# SSv3_outputAmp.net
KiCad netlist of a schematic drawn in EAGLE
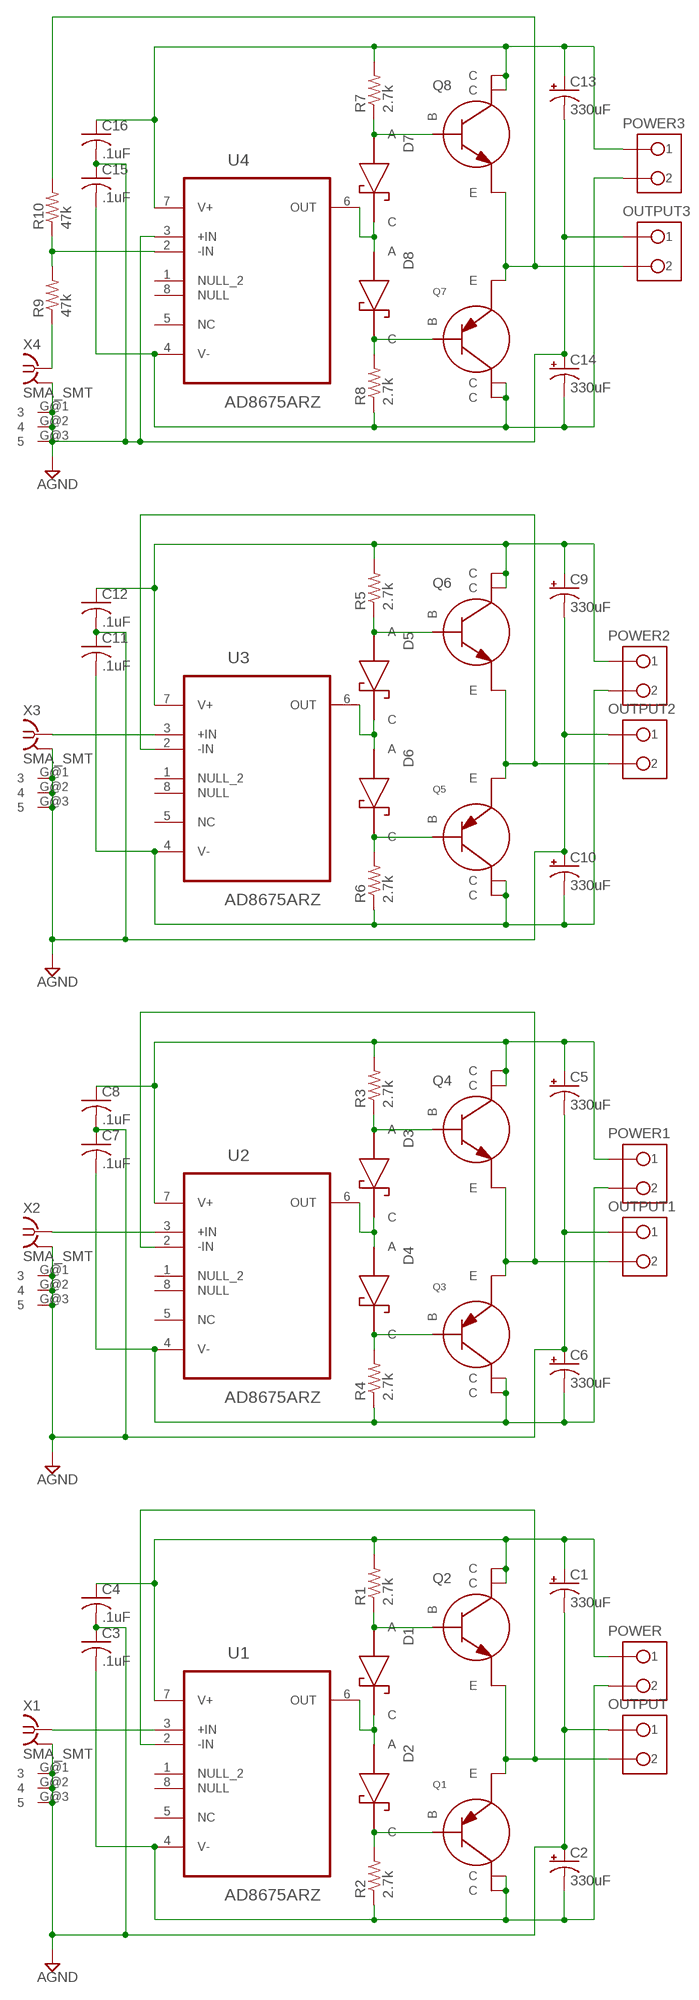
[diagram p0: schematic, sheet 1]

(export (version "E")
  (design (tool "Eeschema 10.0.6"))
  (components
    (comp (ref "C1")
      (value "330uF")
      (footprint "eagle-import:E3,5-8")
      (libsource (lib "eagle-import") (part "CPOL-USE3.5-8"))
    )
    (comp (ref "C2")
      (value "330uF")
      (footprint "eagle-import:E3,5-8")
      (libsource (lib "eagle-import") (part "CPOL-USE3.5-8"))
    )
    (comp (ref "C3")
      (value ".1uF")
      (footprint "eagle-import:C0603")
      (libsource (lib "eagle-import") (part "C-USC0603"))
    )
    (comp (ref "C4")
      (value ".1uF")
      (footprint "eagle-import:C0603")
      (libsource (lib "eagle-import") (part "C-USC0603"))
    )
    (comp (ref "C5")
      (value "330uF")
      (footprint "eagle-import:E3,5-8")
      (libsource (lib "eagle-import") (part "CPOL-USE3.5-8"))
    )
    (comp (ref "C6")
      (value "330uF")
      (footprint "eagle-import:E3,5-8")
      (libsource (lib "eagle-import") (part "CPOL-USE3.5-8"))
    )
    (comp (ref "C7")
      (value ".1uF")
      (footprint "eagle-import:C0603")
      (libsource (lib "eagle-import") (part "C-USC0603"))
    )
    (comp (ref "C8")
      (value ".1uF")
      (footprint "eagle-import:C0603")
      (libsource (lib "eagle-import") (part "C-USC0603"))
    )
    (comp (ref "C9")
      (value "330uF")
      (footprint "eagle-import:E3,5-8")
      (libsource (lib "eagle-import") (part "CPOL-USE3.5-8"))
    )
    (comp (ref "C10")
      (value "330uF")
      (footprint "eagle-import:E3,5-8")
      (libsource (lib "eagle-import") (part "CPOL-USE3.5-8"))
    )
    (comp (ref "C11")
      (value ".1uF")
      (footprint "eagle-import:C0603")
      (libsource (lib "eagle-import") (part "C-USC0603"))
    )
    (comp (ref "C12")
      (value ".1uF")
      (footprint "eagle-import:C0603")
      (libsource (lib "eagle-import") (part "C-USC0603"))
    )
    (comp (ref "C13")
      (value "330uF")
      (footprint "eagle-import:E3,5-8")
      (libsource (lib "eagle-import") (part "CPOL-USE3.5-8"))
    )
    (comp (ref "C14")
      (value "330uF")
      (footprint "eagle-import:E3,5-8")
      (libsource (lib "eagle-import") (part "CPOL-USE3.5-8"))
    )
    (comp (ref "C15")
      (value ".1uF")
      (footprint "eagle-import:C0603")
      (libsource (lib "eagle-import") (part "C-USC0603"))
    )
    (comp (ref "C16")
      (value ".1uF")
      (footprint "eagle-import:C0603")
      (libsource (lib "eagle-import") (part "C-USC0603"))
    )
    (comp (ref "D1")
      (value "1N5819SOD123")
      (footprint "eagle-import:SOD-123")
      (libsource (lib "eagle-import") (part "1N5819SOD123"))
    )
    (comp (ref "D2")
      (value "1N5819SOD123")
      (footprint "eagle-import:SOD-123")
      (libsource (lib "eagle-import") (part "1N5819SOD123"))
    )
    (comp (ref "D3")
      (value "1N5819SOD123")
      (footprint "eagle-import:SOD-123")
      (libsource (lib "eagle-import") (part "1N5819SOD123"))
    )
    (comp (ref "D4")
      (value "1N5819SOD123")
      (footprint "eagle-import:SOD-123")
      (libsource (lib "eagle-import") (part "1N5819SOD123"))
    )
    (comp (ref "D5")
      (value "1N5819SOD123")
      (footprint "eagle-import:SOD-123")
      (libsource (lib "eagle-import") (part "1N5819SOD123"))
    )
    (comp (ref "D6")
      (value "1N5819SOD123")
      (footprint "eagle-import:SOD-123")
      (libsource (lib "eagle-import") (part "1N5819SOD123"))
    )
    (comp (ref "D7")
      (value "1N5819SOD123")
      (footprint "eagle-import:SOD-123")
      (libsource (lib "eagle-import") (part "1N5819SOD123"))
    )
    (comp (ref "D8")
      (value "1N5819SOD123")
      (footprint "eagle-import:SOD-123")
      (libsource (lib "eagle-import") (part "1N5819SOD123"))
    )
    (comp (ref "OUTPUT")
      (value "OST-2P-SCREW-TERMINAL")
      (footprint "eagle-import:OST-2P-SCREW-TERMINAL")
      (libsource (lib "eagle-import") (part "OST-2P-SCREW-TERMINAL"))
    )
    (comp (ref "OUTPUT1")
      (value "OST-2P-SCREW-TERMINAL")
      (footprint "eagle-import:OST-2P-SCREW-TERMINAL")
      (libsource (lib "eagle-import") (part "OST-2P-SCREW-TERMINAL"))
    )
    (comp (ref "OUTPUT2")
      (value "OST-2P-SCREW-TERMINAL")
      (footprint "eagle-import:OST-2P-SCREW-TERMINAL")
      (libsource (lib "eagle-import") (part "OST-2P-SCREW-TERMINAL"))
    )
    (comp (ref "OUTPUT3")
      (value "OST-2P-SCREW-TERMINAL")
      (footprint "eagle-import:OST-2P-SCREW-TERMINAL")
      (libsource (lib "eagle-import") (part "OST-2P-SCREW-TERMINAL"))
    )
    (comp (ref "POWER")
      (value "OST-2P-SCREW-TERMINAL")
      (footprint "eagle-import:OST-2P-SCREW-TERMINAL")
      (libsource (lib "eagle-import") (part "OST-2P-SCREW-TERMINAL"))
    )
    (comp (ref "POWER1")
      (value "OST-2P-SCREW-TERMINAL")
      (footprint "eagle-import:OST-2P-SCREW-TERMINAL")
      (libsource (lib "eagle-import") (part "OST-2P-SCREW-TERMINAL"))
    )
    (comp (ref "POWER2")
      (value "OST-2P-SCREW-TERMINAL")
      (footprint "eagle-import:OST-2P-SCREW-TERMINAL")
      (libsource (lib "eagle-import") (part "OST-2P-SCREW-TERMINAL"))
    )
    (comp (ref "POWER3")
      (value "OST-2P-SCREW-TERMINAL")
      (footprint "eagle-import:OST-2P-SCREW-TERMINAL")
      (libsource (lib "eagle-import") (part "OST-2P-SCREW-TERMINAL"))
    )
    (comp (ref "Q1")
      (value "NJT4030PSOT-223")
      (footprint "eagle-import:SOT223")
      (libsource (lib "eagle-import") (part "NJT4030PSOT-223"))
    )
    (comp (ref "Q2")
      (value "NJT4031NSOT-223")
      (footprint "eagle-import:SOT223")
      (libsource (lib "eagle-import") (part "NJT4031NSOT-223"))
    )
    (comp (ref "Q3")
      (value "NJT4030PSOT-223")
      (footprint "eagle-import:SOT223")
      (libsource (lib "eagle-import") (part "NJT4030PSOT-223"))
    )
    (comp (ref "Q4")
      (value "NJT4031NSOT-223")
      (footprint "eagle-import:SOT223")
      (libsource (lib "eagle-import") (part "NJT4031NSOT-223"))
    )
    (comp (ref "Q5")
      (value "NJT4030PSOT-223")
      (footprint "eagle-import:SOT223")
      (libsource (lib "eagle-import") (part "NJT4030PSOT-223"))
    )
    (comp (ref "Q6")
      (value "NJT4031NSOT-223")
      (footprint "eagle-import:SOT223")
      (libsource (lib "eagle-import") (part "NJT4031NSOT-223"))
    )
    (comp (ref "Q7")
      (value "NJT4030PSOT-223")
      (footprint "eagle-import:SOT223")
      (libsource (lib "eagle-import") (part "NJT4030PSOT-223"))
    )
    (comp (ref "Q8")
      (value "NJT4031NSOT-223")
      (footprint "eagle-import:SOT223")
      (libsource (lib "eagle-import") (part "NJT4031NSOT-223"))
    )
    (comp (ref "R1")
      (value "2.7k")
      (footprint "eagle-import:R0603")
      (libsource (lib "eagle-import") (part "R-US_R0603"))
    )
    (comp (ref "R2")
      (value "2.7k")
      (footprint "eagle-import:R0603")
      (libsource (lib "eagle-import") (part "R-US_R0603"))
    )
    (comp (ref "R3")
      (value "2.7k")
      (footprint "eagle-import:R0603")
      (libsource (lib "eagle-import") (part "R-US_R0603"))
    )
    (comp (ref "R4")
      (value "2.7k")
      (footprint "eagle-import:R0603")
      (libsource (lib "eagle-import") (part "R-US_R0603"))
    )
    (comp (ref "R5")
      (value "2.7k")
      (footprint "eagle-import:R0603")
      (libsource (lib "eagle-import") (part "R-US_R0603"))
    )
    (comp (ref "R6")
      (value "2.7k")
      (footprint "eagle-import:R0603")
      (libsource (lib "eagle-import") (part "R-US_R0603"))
    )
    (comp (ref "R7")
      (value "2.7k")
      (footprint "eagle-import:R0603")
      (libsource (lib "eagle-import") (part "R-US_R0603"))
    )
    (comp (ref "R8")
      (value "2.7k")
      (footprint "eagle-import:R0603")
      (libsource (lib "eagle-import") (part "R-US_R0603"))
    )
    (comp (ref "R9")
      (value "47k")
      (footprint "eagle-import:R0603")
      (libsource (lib "eagle-import") (part "R-US_R0603"))
    )
    (comp (ref "R10")
      (value "47k")
      (footprint "eagle-import:R0603")
      (libsource (lib "eagle-import") (part "R-US_R0603"))
    )
    (comp (ref "U1")
      (value "AD8675ARZ")
      (footprint "eagle-import:SOIC127P600X175-8N")
      (libsource (lib "eagle-import") (part "AD8675ARZ"))
    )
    (comp (ref "U2")
      (value "AD8675ARZ")
      (footprint "eagle-import:SOIC127P600X175-8N")
      (libsource (lib "eagle-import") (part "AD8675ARZ"))
    )
    (comp (ref "U3")
      (value "AD8675ARZ")
      (footprint "eagle-import:SOIC127P600X175-8N")
      (libsource (lib "eagle-import") (part "AD8675ARZ"))
    )
    (comp (ref "U4")
      (value "AD8675ARZ")
      (footprint "eagle-import:SOIC127P600X175-8N")
      (libsource (lib "eagle-import") (part "AD8675ARZ"))
    )
    (comp (ref "X1")
      (value "SMA_SMT")
      (footprint "eagle-import:SIDE_MOUNTSMA")
      (libsource (lib "eagle-import") (part "SMA_SMT"))
    )
    (comp (ref "X2")
      (value "SMA_SMT")
      (footprint "eagle-import:SIDE_MOUNTSMA")
      (libsource (lib "eagle-import") (part "SMA_SMT"))
    )
    (comp (ref "X3")
      (value "SMA_SMT")
      (footprint "eagle-import:SIDE_MOUNTSMA")
      (libsource (lib "eagle-import") (part "SMA_SMT"))
    )
    (comp (ref "X4")
      (value "SMA_SMT")
      (footprint "eagle-import:SIDE_MOUNTSMA")
      (libsource (lib "eagle-import") (part "SMA_SMT"))
    )
  )
  (nets
    (net (code "1") (name "/+12V") (class "Default")
      (node (ref "C1") (pin "+") (pinfunction "+_+") (pintype "passive"))
      (node (ref "C12") (pin "1") (pinfunction "1_1") (pintype "passive"))
      (node (ref "C13") (pin "+") (pinfunction "+_+") (pintype "passive"))
      (node (ref "C16") (pin "1") (pinfunction "1_1") (pintype "passive"))
      (node (ref "C4") (pin "1") (pinfunction "1_1") (pintype "passive"))
      (node (ref "C5") (pin "+") (pinfunction "+_+") (pintype "passive"))
      (node (ref "C8") (pin "1") (pinfunction "1_1") (pintype "passive"))
      (node (ref "C9") (pin "+") (pinfunction "+_+") (pintype "passive"))
      (node (ref "POWER") (pin "P$1") (pinfunction "1_P$1") (pintype "bidirectional"))
      (node (ref "POWER1") (pin "P$1") (pinfunction "1_P$1") (pintype "bidirectional"))
      (node (ref "POWER2") (pin "P$1") (pinfunction "1_P$1") (pintype "bidirectional"))
      (node (ref "POWER3") (pin "P$1") (pinfunction "1_P$1") (pintype "bidirectional"))
      (node (ref "Q2") (pin "2") (pinfunction "C_2") (pintype "bidirectional"))
      (node (ref "Q2") (pin "4") (pinfunction "C_4") (pintype "bidirectional"))
      (node (ref "Q4") (pin "2") (pinfunction "C_2") (pintype "bidirectional"))
      (node (ref "Q4") (pin "4") (pinfunction "C_4") (pintype "bidirectional"))
      (node (ref "Q6") (pin "2") (pinfunction "C_2") (pintype "bidirectional"))
      (node (ref "Q6") (pin "4") (pinfunction "C_4") (pintype "bidirectional"))
      (node (ref "Q8") (pin "2") (pinfunction "C_2") (pintype "bidirectional"))
      (node (ref "Q8") (pin "4") (pinfunction "C_4") (pintype "bidirectional"))
      (node (ref "R1") (pin "2") (pinfunction "2_2") (pintype "passive"))
      (node (ref "R3") (pin "2") (pinfunction "2_2") (pintype "passive"))
      (node (ref "R5") (pin "2") (pinfunction "2_2") (pintype "passive"))
      (node (ref "R7") (pin "2") (pinfunction "2_2") (pintype "passive"))
      (node (ref "U1") (pin "7") (pinfunction "V+_7") (pintype "power_in"))
      (node (ref "U2") (pin "7") (pinfunction "V+_7") (pintype "power_in"))
      (node (ref "U3") (pin "7") (pinfunction "V+_7") (pintype "power_in"))
      (node (ref "U4") (pin "7") (pinfunction "V+_7") (pintype "power_in"))
    )
    (net (code "2") (name "/-12V") (class "Default")
      (node (ref "C10") (pin "-") (pinfunction "-_-") (pintype "passive"))
      (node (ref "C11") (pin "2") (pinfunction "2_2") (pintype "passive"))
      (node (ref "C14") (pin "-") (pinfunction "-_-") (pintype "passive"))
      (node (ref "C15") (pin "2") (pinfunction "2_2") (pintype "passive"))
      (node (ref "C2") (pin "-") (pinfunction "-_-") (pintype "passive"))
      (node (ref "C3") (pin "2") (pinfunction "2_2") (pintype "passive"))
      (node (ref "C6") (pin "-") (pinfunction "-_-") (pintype "passive"))
      (node (ref "C7") (pin "2") (pinfunction "2_2") (pintype "passive"))
      (node (ref "POWER") (pin "P$2") (pinfunction "2_P$2") (pintype "bidirectional"))
      (node (ref "POWER1") (pin "P$2") (pinfunction "2_P$2") (pintype "bidirectional"))
      (node (ref "POWER2") (pin "P$2") (pinfunction "2_P$2") (pintype "bidirectional"))
      (node (ref "POWER3") (pin "P$2") (pinfunction "2_P$2") (pintype "bidirectional"))
      (node (ref "Q1") (pin "2") (pinfunction "C_2") (pintype "bidirectional"))
      (node (ref "Q1") (pin "4") (pinfunction "C_4") (pintype "bidirectional"))
      (node (ref "Q3") (pin "2") (pinfunction "C_2") (pintype "bidirectional"))
      (node (ref "Q3") (pin "4") (pinfunction "C_4") (pintype "bidirectional"))
      (node (ref "Q5") (pin "2") (pinfunction "C_2") (pintype "bidirectional"))
      (node (ref "Q5") (pin "4") (pinfunction "C_4") (pintype "bidirectional"))
      (node (ref "Q7") (pin "2") (pinfunction "C_2") (pintype "bidirectional"))
      (node (ref "Q7") (pin "4") (pinfunction "C_4") (pintype "bidirectional"))
      (node (ref "R2") (pin "1") (pinfunction "1_1") (pintype "passive"))
      (node (ref "R4") (pin "1") (pinfunction "1_1") (pintype "passive"))
      (node (ref "R6") (pin "1") (pinfunction "1_1") (pintype "passive"))
      (node (ref "R8") (pin "1") (pinfunction "1_1") (pintype "passive"))
      (node (ref "U1") (pin "4") (pinfunction "V-_4") (pintype "power_in"))
      (node (ref "U2") (pin "4") (pinfunction "V-_4") (pintype "power_in"))
      (node (ref "U3") (pin "4") (pinfunction "V-_4") (pintype "power_in"))
      (node (ref "U4") (pin "4") (pinfunction "V-_4") (pintype "power_in"))
    )
    (net (code "3") (name "AGND") (class "Default")
      (node (ref "C1") (pin "-") (pinfunction "-_-") (pintype "passive"))
      (node (ref "C10") (pin "+") (pinfunction "+_+") (pintype "passive"))
      (node (ref "C11") (pin "1") (pinfunction "1_1") (pintype "passive"))
      (node (ref "C12") (pin "2") (pinfunction "2_2") (pintype "passive"))
      (node (ref "C13") (pin "-") (pinfunction "-_-") (pintype "passive"))
      (node (ref "C14") (pin "+") (pinfunction "+_+") (pintype "passive"))
      (node (ref "C15") (pin "1") (pinfunction "1_1") (pintype "passive"))
      (node (ref "C16") (pin "2") (pinfunction "2_2") (pintype "passive"))
      (node (ref "C2") (pin "+") (pinfunction "+_+") (pintype "passive"))
      (node (ref "C3") (pin "1") (pinfunction "1_1") (pintype "passive"))
      (node (ref "C4") (pin "2") (pinfunction "2_2") (pintype "passive"))
      (node (ref "C5") (pin "-") (pinfunction "-_-") (pintype "passive"))
      (node (ref "C6") (pin "+") (pinfunction "+_+") (pintype "passive"))
      (node (ref "C7") (pin "1") (pinfunction "1_1") (pintype "passive"))
      (node (ref "C8") (pin "2") (pinfunction "2_2") (pintype "passive"))
      (node (ref "C9") (pin "-") (pinfunction "-_-") (pintype "passive"))
      (node (ref "OUTPUT") (pin "P$1") (pinfunction "1_P$1") (pintype "bidirectional"))
      (node (ref "OUTPUT1") (pin "P$1") (pinfunction "1_P$1") (pintype "bidirectional"))
      (node (ref "OUTPUT2") (pin "P$1") (pinfunction "1_P$1") (pintype "bidirectional"))
      (node (ref "OUTPUT3") (pin "P$1") (pinfunction "1_P$1") (pintype "bidirectional"))
      (node (ref "U4") (pin "3") (pinfunction "+IN_3") (pintype "input"))
      (node (ref "X1") (pin "G@1") (pinfunction "3_G@1") (pintype "bidirectional"))
      (node (ref "X1") (pin "G@2") (pinfunction "4_G@2") (pintype "bidirectional"))
      (node (ref "X1") (pin "G@3") (pinfunction "5_G@3") (pintype "bidirectional"))
      (node (ref "X1") (pin "G@4") (pinfunction "2_G@4") (pintype "bidirectional"))
      (node (ref "X2") (pin "G@1") (pinfunction "3_G@1") (pintype "bidirectional"))
      (node (ref "X2") (pin "G@2") (pinfunction "4_G@2") (pintype "bidirectional"))
      (node (ref "X2") (pin "G@3") (pinfunction "5_G@3") (pintype "bidirectional"))
      (node (ref "X2") (pin "G@4") (pinfunction "2_G@4") (pintype "bidirectional"))
      (node (ref "X3") (pin "G@1") (pinfunction "3_G@1") (pintype "bidirectional"))
      (node (ref "X3") (pin "G@2") (pinfunction "4_G@2") (pintype "bidirectional"))
      (node (ref "X3") (pin "G@3") (pinfunction "5_G@3") (pintype "bidirectional"))
      (node (ref "X3") (pin "G@4") (pinfunction "2_G@4") (pintype "bidirectional"))
      (node (ref "X4") (pin "G@1") (pinfunction "3_G@1") (pintype "bidirectional"))
      (node (ref "X4") (pin "G@2") (pinfunction "4_G@2") (pintype "bidirectional"))
      (node (ref "X4") (pin "G@3") (pinfunction "5_G@3") (pintype "bidirectional"))
      (node (ref "X4") (pin "G@4") (pinfunction "2_G@4") (pintype "bidirectional"))
    )
    (net (code "4") (name "Net-(OUTPUT-2)") (class "Default")
      (node (ref "OUTPUT") (pin "P$2") (pinfunction "2_P$2") (pintype "bidirectional"))
      (node (ref "Q1") (pin "3") (pinfunction "E_3") (pintype "bidirectional"))
      (node (ref "Q2") (pin "3") (pinfunction "E_3") (pintype "bidirectional"))
      (node (ref "U1") (pin "2") (pinfunction "-IN_2") (pintype "input"))
    )
    (net (code "5") (name "Net-(OUTPUT1-2)") (class "Default")
      (node (ref "OUTPUT1") (pin "P$2") (pinfunction "2_P$2") (pintype "bidirectional"))
      (node (ref "Q3") (pin "3") (pinfunction "E_3") (pintype "bidirectional"))
      (node (ref "Q4") (pin "3") (pinfunction "E_3") (pintype "bidirectional"))
      (node (ref "U2") (pin "2") (pinfunction "-IN_2") (pintype "input"))
    )
    (net (code "6") (name "Net-(OUTPUT2-2)") (class "Default")
      (node (ref "OUTPUT2") (pin "P$2") (pinfunction "2_P$2") (pintype "bidirectional"))
      (node (ref "Q5") (pin "3") (pinfunction "E_3") (pintype "bidirectional"))
      (node (ref "Q6") (pin "3") (pinfunction "E_3") (pintype "bidirectional"))
      (node (ref "U3") (pin "2") (pinfunction "-IN_2") (pintype "input"))
    )
    (net (code "7") (name "Net-(OUTPUT3-2)") (class "Default")
      (node (ref "OUTPUT3") (pin "P$2") (pinfunction "2_P$2") (pintype "bidirectional"))
      (node (ref "Q7") (pin "3") (pinfunction "E_3") (pintype "bidirectional"))
      (node (ref "Q8") (pin "3") (pinfunction "E_3") (pintype "bidirectional"))
      (node (ref "R10") (pin "2") (pinfunction "2_2") (pintype "passive"))
    )
    (net (code "8") (name "Net-(Q1-B)") (class "Default")
      (node (ref "D2") (pin "C") (pinfunction "C_C") (pintype "bidirectional"))
      (node (ref "Q1") (pin "1") (pinfunction "B_1") (pintype "bidirectional"))
      (node (ref "R2") (pin "2") (pinfunction "2_2") (pintype "passive"))
    )
    (net (code "9") (name "Net-(Q2-B)") (class "Default")
      (node (ref "D1") (pin "A") (pinfunction "A_A") (pintype "bidirectional"))
      (node (ref "Q2") (pin "1") (pinfunction "B_1") (pintype "bidirectional"))
      (node (ref "R1") (pin "1") (pinfunction "1_1") (pintype "passive"))
    )
    (net (code "10") (name "Net-(Q3-B)") (class "Default")
      (node (ref "D4") (pin "C") (pinfunction "C_C") (pintype "bidirectional"))
      (node (ref "Q3") (pin "1") (pinfunction "B_1") (pintype "bidirectional"))
      (node (ref "R4") (pin "2") (pinfunction "2_2") (pintype "passive"))
    )
    (net (code "11") (name "Net-(Q4-B)") (class "Default")
      (node (ref "D3") (pin "A") (pinfunction "A_A") (pintype "bidirectional"))
      (node (ref "Q4") (pin "1") (pinfunction "B_1") (pintype "bidirectional"))
      (node (ref "R3") (pin "1") (pinfunction "1_1") (pintype "passive"))
    )
    (net (code "12") (name "Net-(Q5-B)") (class "Default")
      (node (ref "D6") (pin "C") (pinfunction "C_C") (pintype "bidirectional"))
      (node (ref "Q5") (pin "1") (pinfunction "B_1") (pintype "bidirectional"))
      (node (ref "R6") (pin "2") (pinfunction "2_2") (pintype "passive"))
    )
    (net (code "13") (name "Net-(Q6-B)") (class "Default")
      (node (ref "D5") (pin "A") (pinfunction "A_A") (pintype "bidirectional"))
      (node (ref "Q6") (pin "1") (pinfunction "B_1") (pintype "bidirectional"))
      (node (ref "R5") (pin "1") (pinfunction "1_1") (pintype "passive"))
    )
    (net (code "14") (name "Net-(Q7-B)") (class "Default")
      (node (ref "D8") (pin "C") (pinfunction "C_C") (pintype "bidirectional"))
      (node (ref "Q7") (pin "1") (pinfunction "B_1") (pintype "bidirectional"))
      (node (ref "R8") (pin "2") (pinfunction "2_2") (pintype "passive"))
    )
    (net (code "15") (name "Net-(Q8-B)") (class "Default")
      (node (ref "D7") (pin "A") (pinfunction "A_A") (pintype "bidirectional"))
      (node (ref "Q8") (pin "1") (pinfunction "B_1") (pintype "bidirectional"))
      (node (ref "R7") (pin "1") (pinfunction "1_1") (pintype "passive"))
    )
    (net (code "16") (name "Net-(R9-Pad1)") (class "Default")
      (node (ref "R9") (pin "1") (pinfunction "1_1") (pintype "passive"))
      (node (ref "X4") (pin "1") (pinfunction "1_1") (pintype "bidirectional"))
    )
    (net (code "17") (name "Net-(U1-+IN)") (class "Default")
      (node (ref "U1") (pin "3") (pinfunction "+IN_3") (pintype "input"))
      (node (ref "X1") (pin "1") (pinfunction "1_1") (pintype "bidirectional"))
    )
    (net (code "18") (name "Net-(U1-OUT)") (class "Default")
      (node (ref "D1") (pin "C") (pinfunction "C_C") (pintype "bidirectional"))
      (node (ref "D2") (pin "A") (pinfunction "A_A") (pintype "bidirectional"))
      (node (ref "U1") (pin "6") (pinfunction "OUT_6") (pintype "output"))
    )
    (net (code "19") (name "Net-(U2-+IN)") (class "Default")
      (node (ref "U2") (pin "3") (pinfunction "+IN_3") (pintype "input"))
      (node (ref "X2") (pin "1") (pinfunction "1_1") (pintype "bidirectional"))
    )
    (net (code "20") (name "Net-(U2-OUT)") (class "Default")
      (node (ref "D3") (pin "C") (pinfunction "C_C") (pintype "bidirectional"))
      (node (ref "D4") (pin "A") (pinfunction "A_A") (pintype "bidirectional"))
      (node (ref "U2") (pin "6") (pinfunction "OUT_6") (pintype "output"))
    )
    (net (code "21") (name "Net-(U3-+IN)") (class "Default")
      (node (ref "U3") (pin "3") (pinfunction "+IN_3") (pintype "input"))
      (node (ref "X3") (pin "1") (pinfunction "1_1") (pintype "bidirectional"))
    )
    (net (code "22") (name "Net-(U3-OUT)") (class "Default")
      (node (ref "D5") (pin "C") (pinfunction "C_C") (pintype "bidirectional"))
      (node (ref "D6") (pin "A") (pinfunction "A_A") (pintype "bidirectional"))
      (node (ref "U3") (pin "6") (pinfunction "OUT_6") (pintype "output"))
    )
    (net (code "23") (name "Net-(U4--IN)") (class "Default")
      (node (ref "R10") (pin "1") (pinfunction "1_1") (pintype "passive"))
      (node (ref "R9") (pin "2") (pinfunction "2_2") (pintype "passive"))
      (node (ref "U4") (pin "2") (pinfunction "-IN_2") (pintype "input"))
    )
    (net (code "24") (name "Net-(U4-OUT)") (class "Default")
      (node (ref "D7") (pin "C") (pinfunction "C_C") (pintype "bidirectional"))
      (node (ref "D8") (pin "A") (pinfunction "A_A") (pintype "bidirectional"))
      (node (ref "U4") (pin "6") (pinfunction "OUT_6") (pintype "output"))
    )
    (net (code "25") (name "unconnected-(U1-NC-Pad5)") (class "Default")
      (node (ref "U1") (pin "5") (pinfunction "NC_5") (pintype "no_connect"))
    )
    (net (code "26") (name "unconnected-(U1-NULL-Pad8)") (class "Default")
      (node (ref "U1") (pin "8") (pinfunction "NULL_8") (pintype "passive"))
    )
    (net (code "27") (name "unconnected-(U1-NULL_2-Pad1)") (class "Default")
      (node (ref "U1") (pin "1") (pinfunction "NULL_2_1") (pintype "passive"))
    )
    (net (code "28") (name "unconnected-(U2-NC-Pad5)") (class "Default")
      (node (ref "U2") (pin "5") (pinfunction "NC_5") (pintype "no_connect"))
    )
    (net (code "29") (name "unconnected-(U2-NULL-Pad8)") (class "Default")
      (node (ref "U2") (pin "8") (pinfunction "NULL_8") (pintype "passive"))
    )
    (net (code "30") (name "unconnected-(U2-NULL_2-Pad1)") (class "Default")
      (node (ref "U2") (pin "1") (pinfunction "NULL_2_1") (pintype "passive"))
    )
    (net (code "31") (name "unconnected-(U3-NC-Pad5)") (class "Default")
      (node (ref "U3") (pin "5") (pinfunction "NC_5") (pintype "no_connect"))
    )
    (net (code "32") (name "unconnected-(U3-NULL-Pad8)") (class "Default")
      (node (ref "U3") (pin "8") (pinfunction "NULL_8") (pintype "passive"))
    )
    (net (code "33") (name "unconnected-(U3-NULL_2-Pad1)") (class "Default")
      (node (ref "U3") (pin "1") (pinfunction "NULL_2_1") (pintype "passive"))
    )
    (net (code "34") (name "unconnected-(U4-NC-Pad5)") (class "Default")
      (node (ref "U4") (pin "5") (pinfunction "NC_5") (pintype "no_connect"))
    )
    (net (code "35") (name "unconnected-(U4-NULL-Pad8)") (class "Default")
      (node (ref "U4") (pin "8") (pinfunction "NULL_8") (pintype "passive"))
    )
    (net (code "36") (name "unconnected-(U4-NULL_2-Pad1)") (class "Default")
      (node (ref "U4") (pin "1") (pinfunction "NULL_2_1") (pintype "passive"))
    )
  )
)
